# Buck_boost_converter.net
KiCad netlist of a schematic drawn in Altium Designer
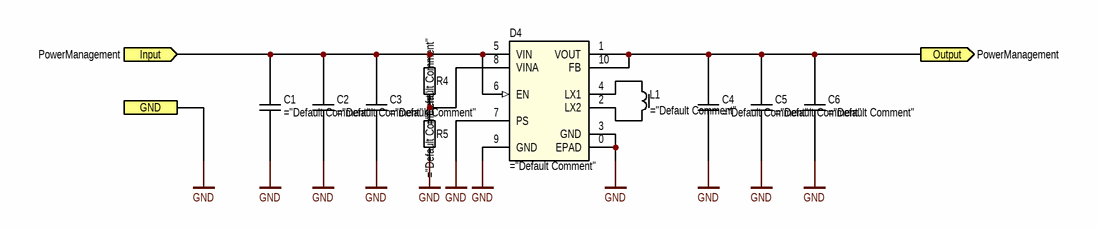
[diagram p0: Buck_boost_converter.SchDoc]

(export (version "E")
  (design (tool "Eeschema 10.0.6"))
  (components
    (comp (ref "C1")
      (value "~")
      (description "CAP CER 1UF 10V X5R 0805")
      (fields (field (name "TOLERANCE") "10 %") (field (name "MANUFACTURER") "YAGEO"))
      (libsource (lib "femtoino") (part "CC0805KKX5R6BB105"))
    )
    (comp (ref "C2")
      (value "~")
      (description "CAP CER 10UF 10V X5R 0805")
      (fields (field (name "TOLERANCE") "10 %") (field (name "MANUFACTURER") "YAGEO"))
      (libsource (lib "femtoino") (part "CC0805KPX5R6BB106"))
    )
    (comp (ref "C3")
      (value "~")
      (description "CAP CER 10UF 10V X5R 0805")
      (fields (field (name "TOLERANCE") "10 %") (field (name "MANUFACTURER") "YAGEO"))
      (libsource (lib "femtoino") (part "CC0805KPX5R6BB106"))
    )
    (comp (ref "C4")
      (value "~")
      (description "CAP CER 10UF 10V X5R 0805")
      (fields (field (name "TOLERANCE") "10 %") (field (name "MANUFACTURER") "YAGEO"))
      (libsource (lib "femtoino") (part "CC0805KPX5R6BB106"))
    )
    (comp (ref "C5")
      (value "~")
      (description "CAP CER 10UF 10V X5R 0805")
      (fields (field (name "TOLERANCE") "10 %") (field (name "MANUFACTURER") "YAGEO"))
      (libsource (lib "femtoino") (part "CC0805KPX5R6BB106"))
    )
    (comp (ref "C6")
      (value "~")
      (description "CAP CER 1UF 10V X5R 0805")
      (fields (field (name "TOLERANCE") "10 %") (field (name "MANUFACTURER") "YAGEO"))
      (libsource (lib "femtoino") (part "CC0805KKX5R6BB105"))
    )
    (comp (ref "D4")
      (value "~")
      (description "IC REG BCK BST 3.3V 800MA 10WDFN")
      (fields (field (name "TOLERANCE") "* %") (field (name "MANUFACTURER") "Richtek USA Inc."))
      (libsource (lib "femtoino") (part "RT6150B-33GQW"))
    )
    (comp (ref "L1")
      (value "~")
      (description "FIXED IND 2.2UH 1.6A 110MOHM SMD")
      (fields (field (name "TOLERANCE") "* %") (field (name "MANUFACTURER") "Würth Elektronik"))
      (libsource (lib "femtoino") (part "74479887222C"))
    )
    (comp (ref "R4")
      (value "~")
      (description "RES 56K OHM 1% 1/10W 0603")
      (fields (field (name "TOLERANCE") "1 %") (field (name "MANUFACTURER") "YAGEO"))
      (libsource (lib "femtoino") (part "RC0603FR-0756KL"))
    )
    (comp (ref "R5")
      (value "~")
      (description "RES 86.6K OHM 1% 1/10W 0603")
      (fields (field (name "TOLERANCE") "1 %") (field (name "MANUFACTURER") "YAGEO"))
      (libsource (lib "femtoino") (part "RC0603FR-0786K6L"))
    )
  )
  (nets
    (net (code "1") (name "/Input") (class "Default")
      (node (ref "C1") (pin "2") (pinfunction "2_2") (pintype "passive"))
      (node (ref "C2") (pin "1") (pinfunction "1_1") (pintype "passive"))
      (node (ref "C3") (pin "1") (pinfunction "1_1") (pintype "passive"))
      (node (ref "D4") (pin "5") (pinfunction "VIN_5") (pintype "passive"))
      (node (ref "D4") (pin "6") (pinfunction "EN_6") (pintype "input"))
      (node (ref "R4") (pin "2") (pinfunction "2_2") (pintype "passive"))
    )
    (net (code "2") (name "/Output") (class "Default")
      (node (ref "C4") (pin "1") (pinfunction "1_1") (pintype "passive"))
      (node (ref "C5") (pin "1") (pinfunction "1_1") (pintype "passive"))
      (node (ref "C6") (pin "2") (pinfunction "2_2") (pintype "passive"))
      (node (ref "D4") (pin "1") (pinfunction "VOUT_1") (pintype "passive"))
      (node (ref "D4") (pin "10") (pinfunction "FB_10") (pintype "passive"))
    )
    (net (code "3") (name "GND") (class "Default")
      (node (ref "C1") (pin "1") (pinfunction "1_1") (pintype "passive"))
      (node (ref "C2") (pin "2") (pinfunction "2_2") (pintype "passive"))
      (node (ref "C3") (pin "2") (pinfunction "2_2") (pintype "passive"))
      (node (ref "C4") (pin "2") (pinfunction "2_2") (pintype "passive"))
      (node (ref "C5") (pin "2") (pinfunction "2_2") (pintype "passive"))
      (node (ref "C6") (pin "1") (pinfunction "1_1") (pintype "passive"))
      (node (ref "D4") (pin "0") (pinfunction "EPAD_0") (pintype "passive"))
      (node (ref "D4") (pin "3") (pinfunction "GND_3") (pintype "passive"))
      (node (ref "D4") (pin "7") (pinfunction "PS_7") (pintype "passive"))
      (node (ref "D4") (pin "9") (pinfunction "GND_9") (pintype "passive"))
      (node (ref "R5") (pin "1") (pinfunction "1_1") (pintype "passive"))
    )
    (net (code "4") (name "Net-(D4-LX1)") (class "Default")
      (node (ref "D4") (pin "4") (pinfunction "LX1_4") (pintype "passive"))
      (node (ref "L1") (pin "1") (pinfunction "1_1") (pintype "passive"))
    )
    (net (code "5") (name "Net-(D4-LX2)") (class "Default")
      (node (ref "D4") (pin "2") (pinfunction "LX2_2") (pintype "passive"))
      (node (ref "L1") (pin "2") (pinfunction "2_2") (pintype "passive"))
    )
    (net (code "6") (name "Net-(D4-VINA)") (class "Default")
      (node (ref "D4") (pin "8") (pinfunction "VINA_8") (pintype "passive"))
      (node (ref "R4") (pin "1") (pinfunction "1_1") (pintype "passive"))
      (node (ref "R5") (pin "2") (pinfunction "2_2") (pintype "passive"))
    )
  )
)
